# HV.net
KiCad netlist of a schematic drawn in Altium Designer
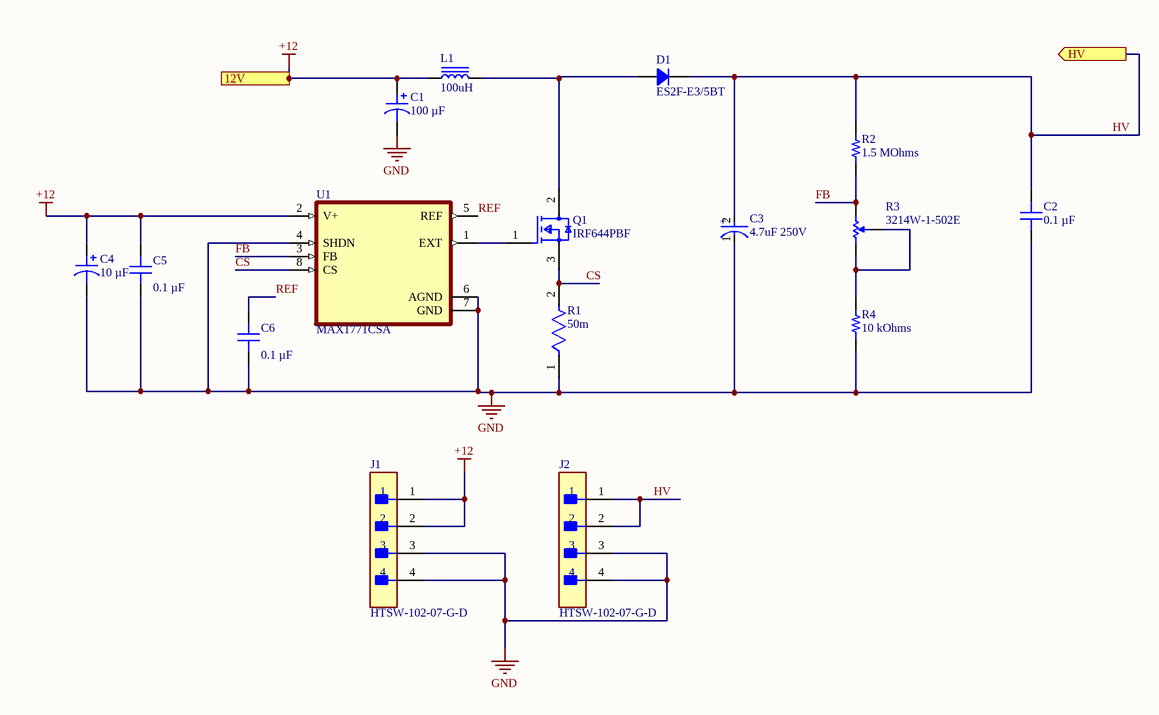
[diagram p0: HV.SchDoc]

(export (version "E")
  (design (tool "Eeschema 10.0.6"))
  (components
    (comp (ref "C1")
      (value "100 µF")
      (footprint "CAP POL 2917_7343")
      (description "TPSD107K020R0150")
      (fields (field (name "PART NUMBER") "T495X106K035ATE200") (field (name "MANUFACTURER") "KEMET"))
      (libsource (lib "Celestial Altium Library - altium_library") (part "Polarised Capacitor"))
    )
    (comp (ref "C2")
      (value "0.1 µF")
      (footprint "CAP 1206_3216 - 0.8MM")
      (description "CAP CER 0.1UF 250V X7R 1206")
      (fields (field (name "PART NUMBER") "CC1206KKX7RYBB104") (field (name "MANUFACTURER") "Yageo"))
      (libsource (lib "Celestial Altium Library - altium_library") (part "Capacitor"))
    )
    (comp (ref "C3")
      (value "4.7uF 250V")
      (footprint "FP-RAD-TH-D_8_0_5-L_11_5-MFG")
      (description "A759KS475M2EBAE496")
      (fields (field (name "TOLERANCE") "20%"))
      (libsource (lib "Altium Content Vault") (part "203bc49f2ac43e59fd269a8c329ed05"))
    )
    (comp (ref "C4")
      (value "10 µF")
      (footprint "CAP POL 2917_7343")
      (description "TPSD106K035R0300")
      (fields (field (name "PART NUMBER") "T495X106K035ATE200") (field (name "MANUFACTURER") "KEMET"))
      (libsource (lib "Celestial Altium Library - altium_library") (part "Polarised Capacitor"))
    )
    (comp (ref "C5")
      (value "0.1 µF")
      (footprint "CAP 0402_1005")
      (description "CAP CER 0.1UF 35V X7R 0402")
      (fields (field (name "PART NUMBER") "CGA2B3X7R1V104M050BB"))
      (libsource (lib "Celestial Altium Library - altium_library") (part "Capacitor"))
    )
    (comp (ref "C6")
      (value "0.1 µF")
      (footprint "CAP 0402_1005")
      (description "CAP CER 0.1UF 35V X7R 0402")
      (fields (field (name "PART NUMBER") "CGA2B3X7R1V104M050BB"))
      (libsource (lib "Celestial Altium Library - altium_library") (part "Capacitor"))
    )
    (comp (ref "D1")
      (value "ES2F-E3/5BT")
      (footprint "DO214AA SMB")
      (description "DIODE GEN PURP 300V 2A DO214AA     ES2F-E3/52TVISHAY\r\nTME")
      (libsource (lib "Celestial Altium Library - altium_library") (part "Diode"))
    )
    (comp (ref "J1")
      (value "HTSW-102-07-G-D")
      (footprint "FP-HTSW-102-07-G-D-MFG")
      (description "CONN HEADER VERT 4POS 2.54MM")
      (fields
        (field (name "MANUFACTURER") "Samtec")
        (field (name "OCTOPART") "https://octopart.com/htsw-102-07-g-d-samtec-10531767")
      )
      (libsource (lib "Altium Content Vault") (part "299a8cea1bdcbc3624fe62c390fa72c"))
    )
    (comp (ref "J2")
      (value "HTSW-102-07-G-D")
      (footprint "FP-HTSW-102-07-G-D-MFG")
      (description "CONN HEADER VERT 4POS 2.54MM")
      (fields
        (field (name "MANUFACTURER") "Samtec")
        (field (name "OCTOPART") "https://octopart.com/htsw-102-07-g-d-samtec-10531767")
      )
      (libsource (lib "Altium Content Vault") (part "299a8cea1bdcbc3624fe62c390fa72c"))
    )
    (comp (ref "L1")
      (value "100uH")
      (footprint "BOURNS SRR1280")
      (description "FIXED IND 100UH 2.1A 150MOHM SMD")
      (fields (field (name "PART NUMBER") "SRR1280-101M"))
      (libsource (lib "Celestial Altium Library - altium_library") (part "Inductor"))
    )
    (comp (ref "Q1")
      (value "IRF644PBF")
      (footprint "FP-E21-0621-MFG")
      (description "N-MOSFET; unipolarny; 250V; 8,5A; 125W; TO220AB")
      (libsource (lib "Altium Content Vault") (part "277670f45256a45703965f138927d09"))
    )
    (comp (ref "R1")
      (value "50m")
      (footprint "FP-CSRN2010-MFG")
      (description "Res Thick Film 2010 50mΩ 1% 1W ±250ppm/°C Molded SMD Plastic T/R")
      (fields (field (name "TOLERANCE") "1%"))
      (libsource (lib "Altium Content Vault") (part "1029c3af85768c4190bb7ad29bc67b5"))
    )
    (comp (ref "R2")
      (value "1.5 MOhms")
      (footprint "RES 2512_6432")
      (description "RES SMD 1.5M OHM 5% 1W 2512")
      (fields
        (field (name "PART NUMBER") "ERJ-1TYJ155U")
        (field (name "MANUFACTURER") "Panasonic Electronic Components")
      )
      (libsource (lib "Celestial Altium Library - altium_library") (part "Resistor"))
    )
    (comp (ref "R3")
      (value "3214W-1-502E")
      (footprint "BOUR-3214W_V")
      (fields (field (name "MANUFACTURER") "Bourns"))
      (libsource (lib "Altium Content Vault") (part "RES-ADJ-3_A"))
    )
    (comp (ref "R4")
      (value "10 kOhms")
      (footprint "RES 0805_2012")
      (description "RES SMD 10K OHM 0.1% 1/10W 0805")
      (fields
        (field (name "PART NUMBER") "CPF0805B10KE")
        (field (name "MANUFACTURER") "TE Connectivity Passive Product")
      )
      (libsource (lib "Celestial Altium Library - altium_library") (part "Resistor"))
    )
    (comp (ref "U1")
      (value "MAX1771CSA")
      (footprint "SOIC127P600X175-8N")
      (fields (field (name "MF") "Maxim Integrated"))
      (libsource (lib "MAX1771CSA") (part "MAX1771CSA"))
    )
  )
  (nets
    (net (code "1") (name "+12") (class "Default")
      (node (ref "C1") (pin "1") (pinfunction "1_1") (pintype "passive"))
      (node (ref "C4") (pin "1") (pinfunction "1_1") (pintype "passive"))
      (node (ref "C5") (pin "2") (pinfunction "2_2") (pintype "passive"))
      (node (ref "J1") (pin "1") (pinfunction "1_1") (pintype "passive"))
      (node (ref "J1") (pin "2") (pinfunction "2_2") (pintype "passive"))
      (node (ref "L1") (pin "1") (pinfunction "1_1") (pintype "passive"))
      (node (ref "U1") (pin "2") (pinfunction "V+_2") (pintype "input"))
    )
    (net (code "2") (name "/CS") (class "Default")
      (node (ref "Q1") (pin "3") (pinfunction "S_3") (pintype "passive"))
      (node (ref "R1") (pin "2") (pinfunction "2_2") (pintype "passive"))
      (node (ref "U1") (pin "8") (pinfunction "CS_8") (pintype "input"))
    )
    (net (code "3") (name "/FB") (class "Default")
      (node (ref "R2") (pin "1") (pinfunction "1_1") (pintype "passive"))
      (node (ref "R3") (pin "3") (pinfunction "3_3") (pintype "passive"))
      (node (ref "U1") (pin "3") (pinfunction "FB_3") (pintype "input"))
    )
    (net (code "4") (name "/HV") (class "Default")
      (node (ref "C2") (pin "2") (pinfunction "2_2") (pintype "passive"))
      (node (ref "C3") (pin "2") (pinfunction "A_2") (pintype "passive"))
      (node (ref "D1") (pin "2") (pinfunction "2_2") (pintype "passive"))
      (node (ref "J2") (pin "1") (pinfunction "1_1") (pintype "passive"))
      (node (ref "J2") (pin "2") (pinfunction "2_2") (pintype "passive"))
      (node (ref "R2") (pin "2") (pinfunction "2_2") (pintype "passive"))
    )
    (net (code "5") (name "/REF") (class "Default")
      (node (ref "C6") (pin "2") (pinfunction "2_2") (pintype "passive"))
      (node (ref "U1") (pin "5") (pinfunction "REF_5") (pintype "output"))
    )
    (net (code "6") (name "GND") (class "Default")
      (node (ref "C1") (pin "2") (pinfunction "2_2") (pintype "passive"))
      (node (ref "C2") (pin "1") (pinfunction "1_1") (pintype "passive"))
      (node (ref "C3") (pin "1") (pinfunction "C_1") (pintype "passive"))
      (node (ref "C4") (pin "2") (pinfunction "2_2") (pintype "passive"))
      (node (ref "C5") (pin "1") (pinfunction "1_1") (pintype "passive"))
      (node (ref "C6") (pin "1") (pinfunction "1_1") (pintype "passive"))
      (node (ref "J1") (pin "3") (pinfunction "3_3") (pintype "passive"))
      (node (ref "J1") (pin "4") (pinfunction "4_4") (pintype "passive"))
      (node (ref "J2") (pin "3") (pinfunction "3_3") (pintype "passive"))
      (node (ref "J2") (pin "4") (pinfunction "4_4") (pintype "passive"))
      (node (ref "R1") (pin "1") (pinfunction "1_1") (pintype "passive"))
      (node (ref "R4") (pin "1") (pinfunction "1_1") (pintype "passive"))
      (node (ref "U1") (pin "4") (pinfunction "SHDN_4") (pintype "input"))
      (node (ref "U1") (pin "6") (pinfunction "AGND_6") (pintype "power_in"))
      (node (ref "U1") (pin "7") (pinfunction "GND_7") (pintype "power_in"))
    )
    (net (code "7") (name "Net-(Q1-D)") (class "Default")
      (node (ref "D1") (pin "1") (pinfunction "1_1") (pintype "passive"))
      (node (ref "L1") (pin "2") (pinfunction "2_2") (pintype "passive"))
      (node (ref "Q1") (pin "2") (pinfunction "D_2") (pintype "passive"))
    )
    (net (code "8") (name "Net-(Q1-G)") (class "Default")
      (node (ref "Q1") (pin "1") (pinfunction "G_1") (pintype "passive"))
      (node (ref "U1") (pin "1") (pinfunction "EXT_1") (pintype "output"))
    )
    (net (code "9") (name "Net-(R3-Pad1)") (class "Default")
      (node (ref "R3") (pin "1") (pinfunction "1_1") (pintype "passive"))
      (node (ref "R3") (pin "2") (pinfunction "2_2") (pintype "passive"))
      (node (ref "R4") (pin "2") (pinfunction "2_2") (pintype "passive"))
    )
  )
)
